# LAN8830_PINOUT.net
KiCad netlist of a schematic drawn in Altium Designer
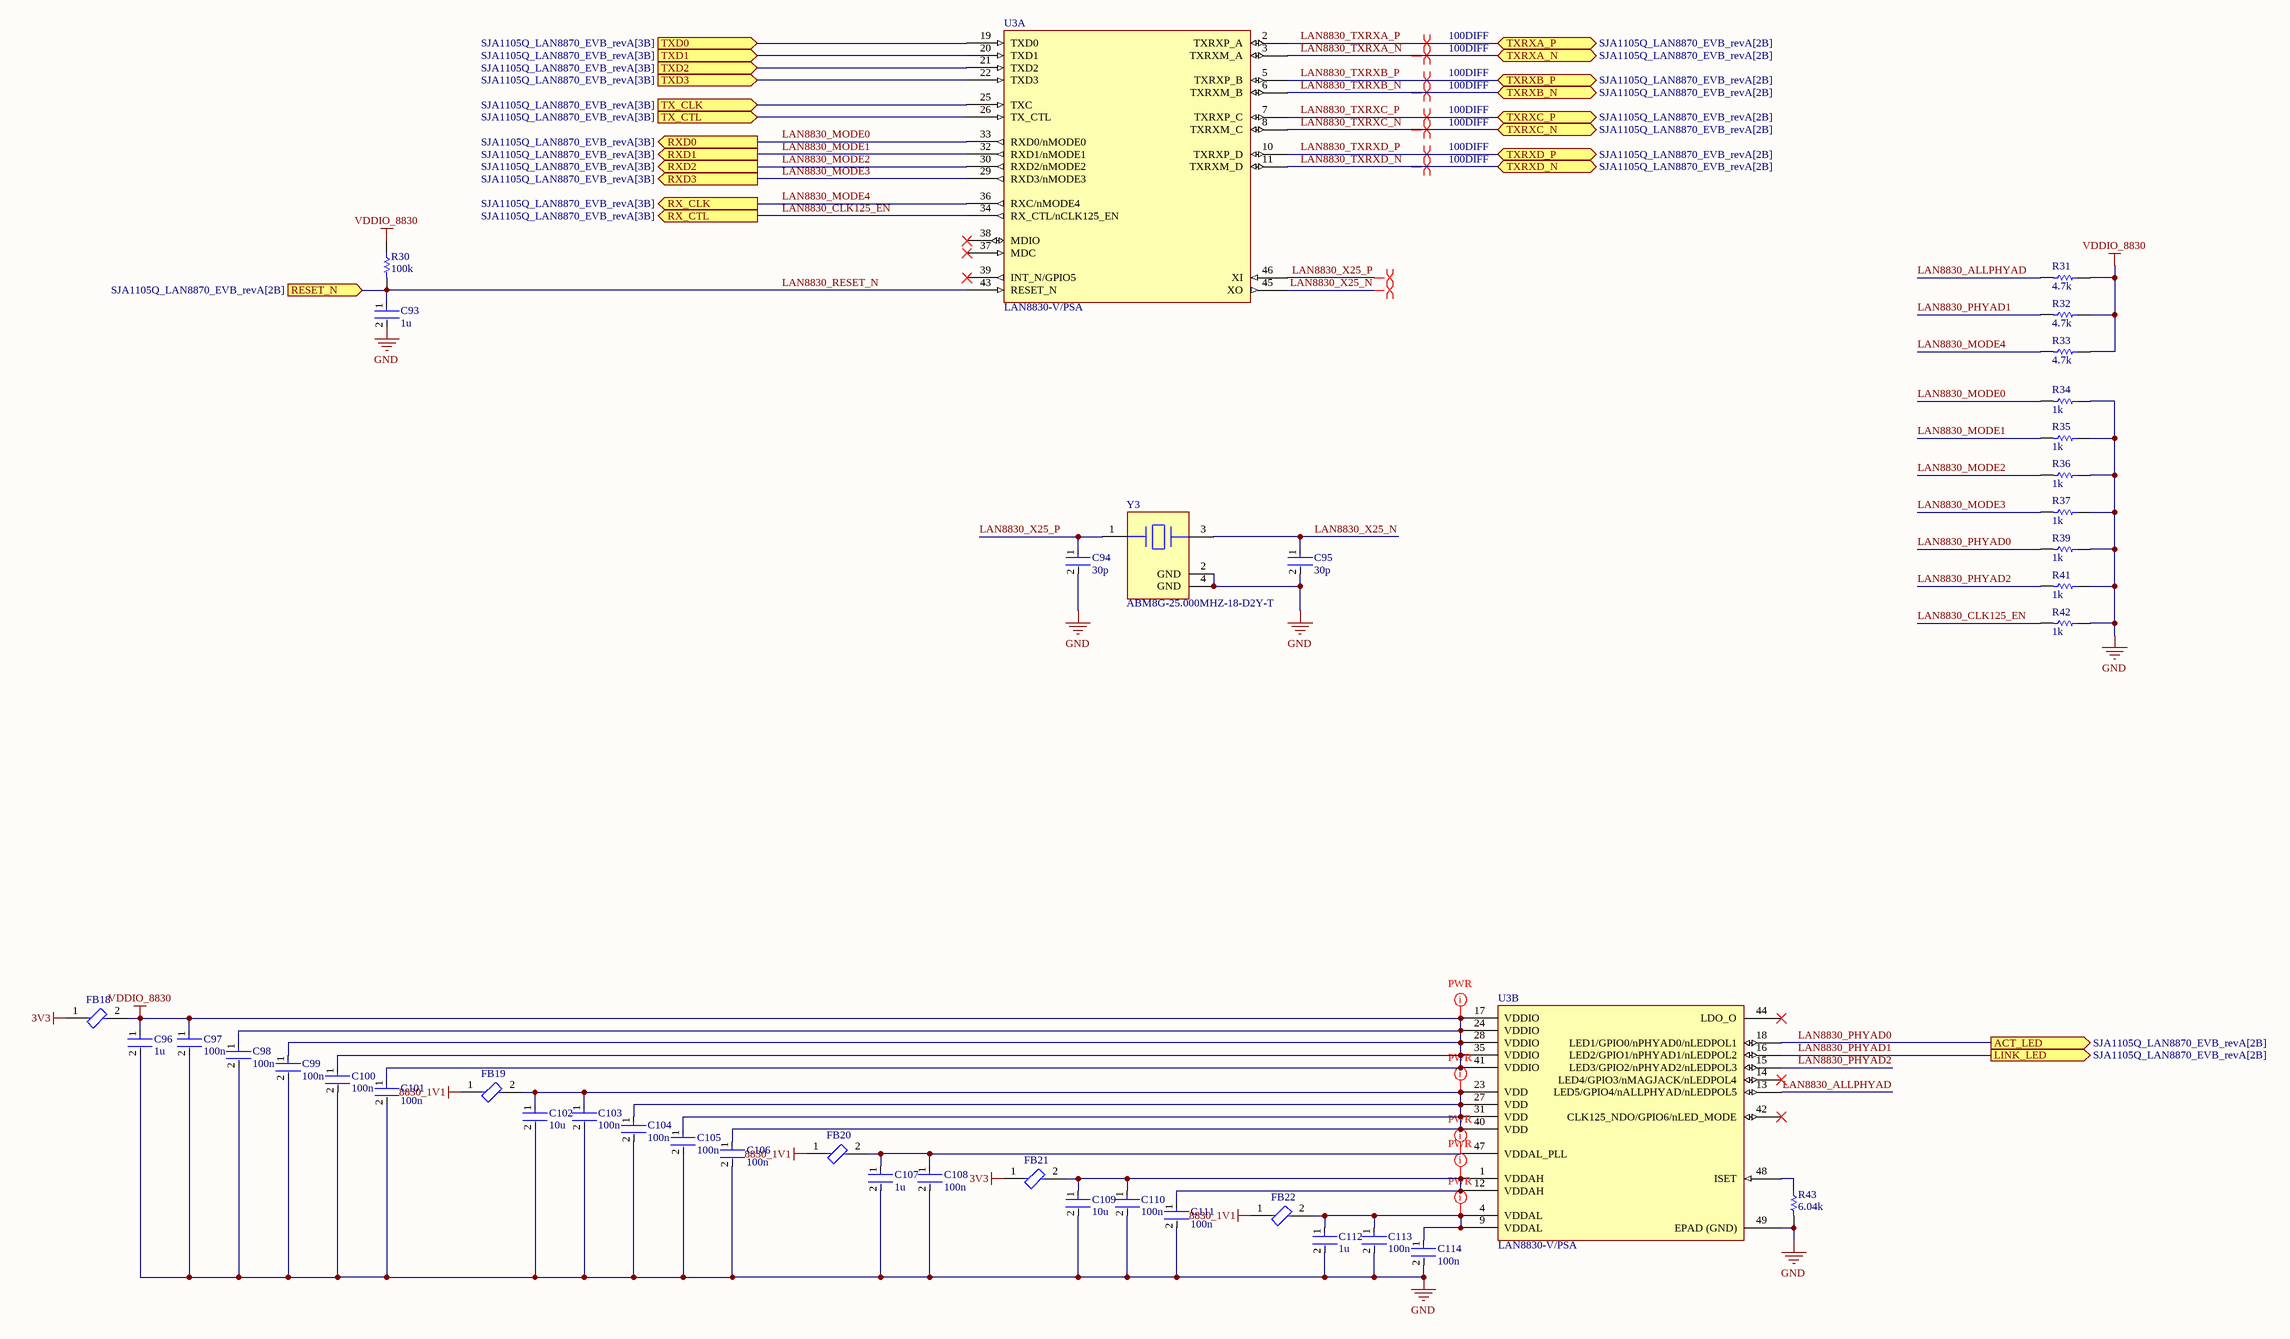
[diagram p0: LAN8830_PINOUT.SchDoc]

(export (version "E")
  (design (tool "Eeschema 10.0.6"))
  (components
    (comp (ref "C93")
      (value "1u")
      (footprint "FP-0402-L_1_0_0_05-W_0_5-IPC_A")
      (description "LARGE PADS, 0402 CAP, CHANGE COMMENT TO MATCH REAL P/N")
      (libsource (lib "Space Concordia") (part "b4654b650e69147ec39a6b967a45e02"))
    )
    (comp (ref "C94")
      (value "30p")
      (footprint "FP-0402-L_1_0_0_05-W_0_5-IPC_A")
      (description "LARGE PADS, 0402 CAP, CHANGE COMMENT TO MATCH REAL P/N")
      (libsource (lib "Space Concordia") (part "b4654b650e69147ec39a6b967a45e02"))
    )
    (comp (ref "C95")
      (value "30p")
      (footprint "FP-0402-L_1_0_0_05-W_0_5-IPC_A")
      (description "LARGE PADS, 0402 CAP, CHANGE COMMENT TO MATCH REAL P/N")
      (libsource (lib "Space Concordia") (part "b4654b650e69147ec39a6b967a45e02"))
    )
    (comp (ref "C96")
      (value "1u")
      (footprint "FP-0402-L_1_0_0_05-W_0_5-IPC_A")
      (description "LARGE PADS, 0402 CAP, CHANGE COMMENT TO MATCH REAL P/N")
      (libsource (lib "Space Concordia") (part "b4654b650e69147ec39a6b967a45e02"))
    )
    (comp (ref "C97")
      (value "100n")
      (footprint "FP-0402-L_1_0_0_05-W_0_5-IPC_A")
      (description "LARGE PADS, 0402 CAP, CHANGE COMMENT TO MATCH REAL P/N")
      (libsource (lib "Space Concordia") (part "b4654b650e69147ec39a6b967a45e02"))
    )
    (comp (ref "C98")
      (value "100n")
      (footprint "FP-0402-L_1_0_0_05-W_0_5-IPC_A")
      (description "LARGE PADS, 0402 CAP, CHANGE COMMENT TO MATCH REAL P/N")
      (libsource (lib "Space Concordia") (part "b4654b650e69147ec39a6b967a45e02"))
    )
    (comp (ref "C99")
      (value "100n")
      (footprint "FP-0402-L_1_0_0_05-W_0_5-IPC_A")
      (description "LARGE PADS, 0402 CAP, CHANGE COMMENT TO MATCH REAL P/N")
      (libsource (lib "Space Concordia") (part "b4654b650e69147ec39a6b967a45e02"))
    )
    (comp (ref "C100")
      (value "100n")
      (footprint "FP-0402-L_1_0_0_05-W_0_5-IPC_A")
      (description "LARGE PADS, 0402 CAP, CHANGE COMMENT TO MATCH REAL P/N")
      (libsource (lib "Space Concordia") (part "b4654b650e69147ec39a6b967a45e02"))
    )
    (comp (ref "C101")
      (value "100n")
      (footprint "FP-0402-L_1_0_0_05-W_0_5-IPC_A")
      (description "LARGE PADS, 0402 CAP, CHANGE COMMENT TO MATCH REAL P/N")
      (libsource (lib "Space Concordia") (part "b4654b650e69147ec39a6b967a45e02"))
    )
    (comp (ref "C102")
      (value "10u")
      (footprint "FP-0402-L_1_0_0_05-W_0_5-IPC_A")
      (description "LARGE PADS, 0402 CAP, CHANGE COMMENT TO MATCH REAL P/N")
      (libsource (lib "Space Concordia") (part "b4654b650e69147ec39a6b967a45e02"))
    )
    (comp (ref "C103")
      (value "100n")
      (footprint "FP-0402-L_1_0_0_05-W_0_5-IPC_A")
      (description "LARGE PADS, 0402 CAP, CHANGE COMMENT TO MATCH REAL P/N")
      (libsource (lib "Space Concordia") (part "b4654b650e69147ec39a6b967a45e02"))
    )
    (comp (ref "C104")
      (value "100n")
      (footprint "FP-0402-L_1_0_0_05-W_0_5-IPC_A")
      (description "LARGE PADS, 0402 CAP, CHANGE COMMENT TO MATCH REAL P/N")
      (libsource (lib "Space Concordia") (part "b4654b650e69147ec39a6b967a45e02"))
    )
    (comp (ref "C105")
      (value "100n")
      (footprint "FP-0402-L_1_0_0_05-W_0_5-IPC_A")
      (description "LARGE PADS, 0402 CAP, CHANGE COMMENT TO MATCH REAL P/N")
      (libsource (lib "Space Concordia") (part "b4654b650e69147ec39a6b967a45e02"))
    )
    (comp (ref "C106")
      (value "100n")
      (footprint "FP-0402-L_1_0_0_05-W_0_5-IPC_A")
      (description "LARGE PADS, 0402 CAP, CHANGE COMMENT TO MATCH REAL P/N")
      (libsource (lib "Space Concordia") (part "b4654b650e69147ec39a6b967a45e02"))
    )
    (comp (ref "C107")
      (value "1u")
      (footprint "FP-0402-L_1_0_0_05-W_0_5-IPC_A")
      (description "LARGE PADS, 0402 CAP, CHANGE COMMENT TO MATCH REAL P/N")
      (libsource (lib "Space Concordia") (part "b4654b650e69147ec39a6b967a45e02"))
    )
    (comp (ref "C108")
      (value "100n")
      (footprint "FP-0402-L_1_0_0_05-W_0_5-IPC_A")
      (description "LARGE PADS, 0402 CAP, CHANGE COMMENT TO MATCH REAL P/N")
      (libsource (lib "Space Concordia") (part "b4654b650e69147ec39a6b967a45e02"))
    )
    (comp (ref "C109")
      (value "10u")
      (footprint "FP-0402-L_1_0_0_05-W_0_5-IPC_A")
      (description "LARGE PADS, 0402 CAP, CHANGE COMMENT TO MATCH REAL P/N")
      (libsource (lib "Space Concordia") (part "b4654b650e69147ec39a6b967a45e02"))
    )
    (comp (ref "C110")
      (value "100n")
      (footprint "FP-0402-L_1_0_0_05-W_0_5-IPC_A")
      (description "LARGE PADS, 0402 CAP, CHANGE COMMENT TO MATCH REAL P/N")
      (libsource (lib "Space Concordia") (part "b4654b650e69147ec39a6b967a45e02"))
    )
    (comp (ref "C111")
      (value "100n")
      (footprint "FP-0402-L_1_0_0_05-W_0_5-IPC_A")
      (description "LARGE PADS, 0402 CAP, CHANGE COMMENT TO MATCH REAL P/N")
      (libsource (lib "Space Concordia") (part "b4654b650e69147ec39a6b967a45e02"))
    )
    (comp (ref "C112")
      (value "1u")
      (footprint "FP-0402-L_1_0_0_05-W_0_5-IPC_A")
      (description "LARGE PADS, 0402 CAP, CHANGE COMMENT TO MATCH REAL P/N")
      (libsource (lib "Space Concordia") (part "b4654b650e69147ec39a6b967a45e02"))
    )
    (comp (ref "C113")
      (value "100n")
      (footprint "FP-0402-L_1_0_0_05-W_0_5-IPC_A")
      (description "LARGE PADS, 0402 CAP, CHANGE COMMENT TO MATCH REAL P/N")
      (libsource (lib "Space Concordia") (part "b4654b650e69147ec39a6b967a45e02"))
    )
    (comp (ref "C114")
      (value "100n")
      (footprint "FP-0402-L_1_0_0_05-W_0_5-IPC_A")
      (description "LARGE PADS, 0402 CAP, CHANGE COMMENT TO MATCH REAL P/N")
      (libsource (lib "Space Concordia") (part "b4654b650e69147ec39a6b967a45e02"))
    )
    (comp (ref "FB18")
      (value "BLM18KG331SH1D")
      (footprint "FP-BLM18-0_15-t0_8-IPC_B")
      (description "Chip Ferrite Bead, 0603, 330Ω @ 100MHz, 0.08Ω, 25%, 1.7A")
      (libsource (lib "Altium Content Vault") (part "5f30dd21d616792df468990f7003faa"))
    )
    (comp (ref "FB19")
      (value "BLM18KG331SH1D")
      (footprint "FP-BLM18-0_15-t0_8-IPC_B")
      (description "Chip Ferrite Bead, 0603, 330Ω @ 100MHz, 0.08Ω, 25%, 1.7A")
      (libsource (lib "Altium Content Vault") (part "5f30dd21d616792df468990f7003faa"))
    )
    (comp (ref "FB20")
      (value "BLM18KG331SH1D")
      (footprint "FP-BLM18-0_15-t0_8-IPC_B")
      (description "Chip Ferrite Bead, 0603, 330Ω @ 100MHz, 0.08Ω, 25%, 1.7A")
      (libsource (lib "Altium Content Vault") (part "5f30dd21d616792df468990f7003faa"))
    )
    (comp (ref "FB21")
      (value "BLM18KG331SH1D")
      (footprint "FP-BLM18-0_15-t0_8-IPC_B")
      (description "Chip Ferrite Bead, 0603, 330Ω @ 100MHz, 0.08Ω, 25%, 1.7A")
      (libsource (lib "Altium Content Vault") (part "5f30dd21d616792df468990f7003faa"))
    )
    (comp (ref "FB22")
      (value "BLM18KG331SH1D")
      (footprint "FP-BLM18-0_15-t0_8-IPC_B")
      (description "Chip Ferrite Bead, 0603, 330Ω @ 100MHz, 0.08Ω, 25%, 1.7A")
      (libsource (lib "Altium Content Vault") (part "5f30dd21d616792df468990f7003faa"))
    )
    (comp (ref "R30")
      (value "100k")
      (footprint "R0603B")
      (description "Resistor")
      (libsource (lib "Space Concordia") (part "Resistor"))
    )
    (comp (ref "R31")
      (value "4.7k")
      (footprint "R0603B")
      (description "Resistor")
      (libsource (lib "Space Concordia") (part "Resistor"))
    )
    (comp (ref "R32")
      (value "4.7k")
      (footprint "R0603B")
      (description "Resistor")
      (libsource (lib "Space Concordia") (part "Resistor"))
    )
    (comp (ref "R33")
      (value "4.7k")
      (footprint "R0603B")
      (description "Resistor")
      (libsource (lib "Space Concordia") (part "Resistor"))
    )
    (comp (ref "R34")
      (value "1k")
      (footprint "R0603B")
      (description "Resistor")
      (libsource (lib "Space Concordia") (part "Resistor"))
    )
    (comp (ref "R35")
      (value "1k")
      (footprint "R0603B")
      (description "Resistor")
      (libsource (lib "Space Concordia") (part "Resistor"))
    )
    (comp (ref "R36")
      (value "1k")
      (footprint "R0603B")
      (description "Resistor")
      (libsource (lib "Space Concordia") (part "Resistor"))
    )
    (comp (ref "R37")
      (value "1k")
      (footprint "R0603B")
      (description "Resistor")
      (libsource (lib "Space Concordia") (part "Resistor"))
    )
    (comp (ref "R39")
      (value "1k")
      (footprint "R0603B")
      (description "Resistor")
      (libsource (lib "Space Concordia") (part "Resistor"))
    )
    (comp (ref "R41")
      (value "1k")
      (footprint "R0603B")
      (description "Resistor")
      (libsource (lib "Space Concordia") (part "Resistor"))
    )
    (comp (ref "R42")
      (value "1k")
      (footprint "R0603B")
      (description "Resistor")
      (libsource (lib "Space Concordia") (part "Resistor"))
    )
    (comp (ref "R43")
      (value "6.04k")
      (footprint "R0603B")
      (description "Resistor")
      (libsource (lib "Space Concordia") (part "Resistor"))
    )
    (comp (ref "U3")
      (value "LAN8830-V/PSA")
      (footprint "QFN50P700X700X100_HS-49N")
      (description "LAN8830 Series RGMII Interface Gigabit Ethernet Transceiver - VQFN-48")
      (libsource (lib "Space Concordia") (part "LAN8830-V_PSA"))
    )
    (comp (ref "Y3")
      (value "ABM8G-25.000MHZ-18-D2Y-T")
      (footprint "FP-ABM8G-MFG")
      (description "Crystal 25MHz ±20ppm (Tol) ±30ppm (Stability) 18pF FUND 60Ω 4-Pin SMD T/R")
      (fields (field (name "TOLERANCE") "20ppm"))
      (libsource (lib "Altium Content Vault") (part "48e526d86b7f2615d98721063c72f49"))
    )
  )
  (nets
    (net (code "1") (name "/LAN8830_ALLPHYAD") (class "Default")
      (node (ref "R31") (pin "2") (pinfunction "2_2") (pintype "passive"))
      (node (ref "U3") (pin "13") (pinfunction "LED5/GPIO4/nALLPHYAD/nLEDPOL5_13") (pintype "bidirectional"))
    )
    (net (code "2") (name "/LAN8830_CLK125_EN") (class "Default")
      (node (ref "R42") (pin "2") (pinfunction "2_2") (pintype "passive"))
      (node (ref "U3") (pin "34") (pinfunction "RX_CTL/nCLK125_EN_34") (pintype "output"))
    )
    (net (code "3") (name "/LAN8830_MODE0") (class "Default")
      (node (ref "R34") (pin "2") (pinfunction "2_2") (pintype "passive"))
      (node (ref "U3") (pin "33") (pinfunction "RXD0/nMODE0_33") (pintype "output"))
    )
    (net (code "4") (name "/LAN8830_MODE1") (class "Default")
      (node (ref "R35") (pin "2") (pinfunction "2_2") (pintype "passive"))
      (node (ref "U3") (pin "32") (pinfunction "RXD1/nMODE1_32") (pintype "output"))
    )
    (net (code "5") (name "/LAN8830_MODE2") (class "Default")
      (node (ref "R36") (pin "2") (pinfunction "2_2") (pintype "passive"))
      (node (ref "U3") (pin "30") (pinfunction "RXD2/nMODE2_30") (pintype "output"))
    )
    (net (code "6") (name "/LAN8830_MODE3") (class "Default")
      (node (ref "R37") (pin "2") (pinfunction "2_2") (pintype "passive"))
      (node (ref "U3") (pin "29") (pinfunction "RXD3/nMODE3_29") (pintype "output"))
    )
    (net (code "7") (name "/LAN8830_MODE4") (class "Default")
      (node (ref "R33") (pin "2") (pinfunction "2_2") (pintype "passive"))
      (node (ref "U3") (pin "36") (pinfunction "RXC/nMODE4_36") (pintype "output"))
    )
    (net (code "8") (name "/LAN8830_PHYAD0") (class "Default")
      (node (ref "R39") (pin "2") (pinfunction "2_2") (pintype "passive"))
      (node (ref "U3") (pin "18") (pinfunction "LED1/GPIO0/nPHYAD0/nLEDPOL1_18") (pintype "bidirectional"))
    )
    (net (code "9") (name "/LAN8830_PHYAD1") (class "Default")
      (node (ref "R32") (pin "2") (pinfunction "2_2") (pintype "passive"))
      (node (ref "U3") (pin "16") (pinfunction "LED2/GPIO1/nPHYAD1/nLEDPOL2_16") (pintype "bidirectional"))
    )
    (net (code "10") (name "/LAN8830_PHYAD2") (class "Default")
      (node (ref "R41") (pin "2") (pinfunction "2_2") (pintype "passive"))
      (node (ref "U3") (pin "15") (pinfunction "LED3/GPIO2/nPHYAD2/nLEDPOL3_15") (pintype "bidirectional"))
    )
    (net (code "11") (name "/LAN8830_RESET_N") (class "Default")
      (node (ref "C93") (pin "1") (pinfunction "1_1") (pintype "passive"))
      (node (ref "R30") (pin "2") (pinfunction "2_2") (pintype "passive"))
      (node (ref "U3") (pin "43") (pinfunction "RESET_N_43") (pintype "input"))
    )
    (net (code "12") (name "/LAN8830_TXRXA_N") (class "Default")
      (node (ref "U3") (pin "3") (pinfunction "TXRXM_A_3") (pintype "bidirectional"))
    )
    (net (code "13") (name "/LAN8830_TXRXA_P") (class "Default")
      (node (ref "U3") (pin "2") (pinfunction "TXRXP_A_2") (pintype "bidirectional"))
    )
    (net (code "14") (name "/LAN8830_TXRXB_N") (class "Default")
      (node (ref "U3") (pin "6") (pinfunction "TXRXM_B_6") (pintype "bidirectional"))
    )
    (net (code "15") (name "/LAN8830_TXRXB_P") (class "Default")
      (node (ref "U3") (pin "5") (pinfunction "TXRXP_B_5") (pintype "bidirectional"))
    )
    (net (code "16") (name "/LAN8830_TXRXC_N") (class "Default")
      (node (ref "U3") (pin "8") (pinfunction "TXRXM_C_8") (pintype "bidirectional"))
    )
    (net (code "17") (name "/LAN8830_TXRXC_P") (class "Default")
      (node (ref "U3") (pin "7") (pinfunction "TXRXP_C_7") (pintype "bidirectional"))
    )
    (net (code "18") (name "/LAN8830_TXRXD_N") (class "Default")
      (node (ref "U3") (pin "11") (pinfunction "TXRXM_D_11") (pintype "bidirectional"))
    )
    (net (code "19") (name "/LAN8830_TXRXD_P") (class "Default")
      (node (ref "U3") (pin "10") (pinfunction "TXRXP_D_10") (pintype "bidirectional"))
    )
    (net (code "20") (name "/LAN8830_X25_N") (class "Default")
      (node (ref "C95") (pin "1") (pinfunction "1_1") (pintype "passive"))
      (node (ref "U3") (pin "45") (pinfunction "XO_45") (pintype "output"))
      (node (ref "Y3") (pin "3") (pinfunction "3_3") (pintype "passive"))
    )
    (net (code "21") (name "/LAN8830_X25_P") (class "Default")
      (node (ref "C94") (pin "1") (pinfunction "1_1") (pintype "passive"))
      (node (ref "U3") (pin "46") (pinfunction "XI_46") (pintype "input"))
      (node (ref "Y3") (pin "1") (pinfunction "1_1") (pintype "passive"))
    )
    (net (code "22") (name "/TXD0") (class "Default")
      (node (ref "U3") (pin "19") (pinfunction "TXD0_19") (pintype "input"))
    )
    (net (code "23") (name "/TXD1") (class "Default")
      (node (ref "U3") (pin "20") (pinfunction "TXD1_20") (pintype "input"))
    )
    (net (code "24") (name "/TXD2") (class "Default")
      (node (ref "U3") (pin "21") (pinfunction "TXD2_21") (pintype "input"))
    )
    (net (code "25") (name "/TXD3") (class "Default")
      (node (ref "U3") (pin "22") (pinfunction "TXD3_22") (pintype "input"))
    )
    (net (code "26") (name "/TX_CLK") (class "Default")
      (node (ref "U3") (pin "25") (pinfunction "TXC_25") (pintype "input"))
    )
    (net (code "27") (name "/TX_CTL") (class "Default")
      (node (ref "U3") (pin "26") (pinfunction "TX_CTL_26") (pintype "input"))
    )
    (net (code "28") (name "3V3") (class "Default")
      (node (ref "FB18") (pin "1") (pinfunction "1_1") (pintype "passive"))
      (node (ref "FB21") (pin "1") (pinfunction "1_1") (pintype "passive"))
    )
    (net (code "29") (name "8830_1V1") (class "Default")
      (node (ref "FB19") (pin "1") (pinfunction "1_1") (pintype "passive"))
      (node (ref "FB20") (pin "1") (pinfunction "1_1") (pintype "passive"))
      (node (ref "FB22") (pin "1") (pinfunction "1_1") (pintype "passive"))
    )
    (net (code "30") (name "GND") (class "Default")
      (node (ref "C100") (pin "2") (pinfunction "2_2") (pintype "passive"))
      (node (ref "C101") (pin "2") (pinfunction "2_2") (pintype "passive"))
      (node (ref "C102") (pin "2") (pinfunction "2_2") (pintype "passive"))
      (node (ref "C103") (pin "2") (pinfunction "2_2") (pintype "passive"))
      (node (ref "C104") (pin "2") (pinfunction "2_2") (pintype "passive"))
      (node (ref "C105") (pin "2") (pinfunction "2_2") (pintype "passive"))
      (node (ref "C106") (pin "2") (pinfunction "2_2") (pintype "passive"))
      (node (ref "C107") (pin "2") (pinfunction "2_2") (pintype "passive"))
      (node (ref "C108") (pin "2") (pinfunction "2_2") (pintype "passive"))
      (node (ref "C109") (pin "2") (pinfunction "2_2") (pintype "passive"))
      (node (ref "C110") (pin "2") (pinfunction "2_2") (pintype "passive"))
      (node (ref "C111") (pin "2") (pinfunction "2_2") (pintype "passive"))
      (node (ref "C112") (pin "2") (pinfunction "2_2") (pintype "passive"))
      (node (ref "C113") (pin "2") (pinfunction "2_2") (pintype "passive"))
      (node (ref "C114") (pin "2") (pinfunction "2_2") (pintype "passive"))
      (node (ref "C93") (pin "2") (pinfunction "2_2") (pintype "passive"))
      (node (ref "C94") (pin "2") (pinfunction "2_2") (pintype "passive"))
      (node (ref "C95") (pin "2") (pinfunction "2_2") (pintype "passive"))
      (node (ref "C96") (pin "2") (pinfunction "2_2") (pintype "passive"))
      (node (ref "C97") (pin "2") (pinfunction "2_2") (pintype "passive"))
      (node (ref "C98") (pin "2") (pinfunction "2_2") (pintype "passive"))
      (node (ref "C99") (pin "2") (pinfunction "2_2") (pintype "passive"))
      (node (ref "R34") (pin "1") (pinfunction "1_1") (pintype "passive"))
      (node (ref "R35") (pin "1") (pinfunction "1_1") (pintype "passive"))
      (node (ref "R36") (pin "1") (pinfunction "1_1") (pintype "passive"))
      (node (ref "R37") (pin "1") (pinfunction "1_1") (pintype "passive"))
      (node (ref "R39") (pin "1") (pinfunction "1_1") (pintype "passive"))
      (node (ref "R41") (pin "1") (pinfunction "1_1") (pintype "passive"))
      (node (ref "R42") (pin "1") (pinfunction "1_1") (pintype "passive"))
      (node (ref "R43") (pin "2") (pinfunction "2_2") (pintype "passive"))
      (node (ref "U3") (pin "49") (pinfunction "EPAD_(GND)_49") (pintype "power_in"))
      (node (ref "Y3") (pin "2") (pinfunction "GND_2") (pintype "power_in"))
      (node (ref "Y3") (pin "4") (pinfunction "GND_4") (pintype "power_in"))
    )
    (net (code "31") (name "Net-(C102-Pad1)") (class "Default")
      (node (ref "C102") (pin "1") (pinfunction "1_1") (pintype "passive"))
      (node (ref "C103") (pin "1") (pinfunction "1_1") (pintype "passive"))
      (node (ref "C104") (pin "1") (pinfunction "1_1") (pintype "passive"))
      (node (ref "C105") (pin "1") (pinfunction "1_1") (pintype "passive"))
      (node (ref "C106") (pin "1") (pinfunction "1_1") (pintype "passive"))
      (node (ref "FB19") (pin "2") (pinfunction "2_2") (pintype "passive"))
      (node (ref "U3") (pin "23") (pinfunction "VDD_23") (pintype "power_in"))
      (node (ref "U3") (pin "27") (pinfunction "VDD_27") (pintype "power_in"))
      (node (ref "U3") (pin "31") (pinfunction "VDD_31") (pintype "power_in"))
      (node (ref "U3") (pin "40") (pinfunction "VDD_40") (pintype "power_in"))
    )
    (net (code "32") (name "Net-(C109-Pad1)") (class "Default")
      (node (ref "C109") (pin "1") (pinfunction "1_1") (pintype "passive"))
      (node (ref "C110") (pin "1") (pinfunction "1_1") (pintype "passive"))
      (node (ref "C111") (pin "1") (pinfunction "1_1") (pintype "passive"))
      (node (ref "FB21") (pin "2") (pinfunction "2_2") (pintype "passive"))
      (node (ref "U3") (pin "1") (pinfunction "VDDAH_1") (pintype "power_in"))
      (node (ref "U3") (pin "12") (pinfunction "VDDAH_12") (pintype "power_in"))
    )
    (net (code "33") (name "Net-(C112-Pad1)") (class "Default")
      (node (ref "C112") (pin "1") (pinfunction "1_1") (pintype "passive"))
      (node (ref "C113") (pin "1") (pinfunction "1_1") (pintype "passive"))
      (node (ref "C114") (pin "1") (pinfunction "1_1") (pintype "passive"))
      (node (ref "FB22") (pin "2") (pinfunction "2_2") (pintype "passive"))
      (node (ref "U3") (pin "4") (pinfunction "VDDAL_4") (pintype "power_in"))
      (node (ref "U3") (pin "9") (pinfunction "VDDAL_9") (pintype "power_in"))
    )
    (net (code "34") (name "Net-(U3B-ISET)") (class "Default")
      (node (ref "R43") (pin "1") (pinfunction "1_1") (pintype "passive"))
      (node (ref "U3") (pin "48") (pinfunction "ISET_48") (pintype "input"))
    )
    (net (code "35") (name "Net-(U3B-VDDAL_PLL)") (class "Default")
      (node (ref "C107") (pin "1") (pinfunction "1_1") (pintype "passive"))
      (node (ref "C108") (pin "1") (pinfunction "1_1") (pintype "passive"))
      (node (ref "FB20") (pin "2") (pinfunction "2_2") (pintype "passive"))
      (node (ref "U3") (pin "47") (pinfunction "VDDAL_PLL_47") (pintype "power_in"))
    )
    (net (code "36") (name "VDDIO_8830") (class "Default")
      (node (ref "C100") (pin "1") (pinfunction "1_1") (pintype "passive"))
      (node (ref "C101") (pin "1") (pinfunction "1_1") (pintype "passive"))
      (node (ref "C96") (pin "1") (pinfunction "1_1") (pintype "passive"))
      (node (ref "C97") (pin "1") (pinfunction "1_1") (pintype "passive"))
      (node (ref "C98") (pin "1") (pinfunction "1_1") (pintype "passive"))
      (node (ref "C99") (pin "1") (pinfunction "1_1") (pintype "passive"))
      (node (ref "FB18") (pin "2") (pinfunction "2_2") (pintype "passive"))
      (node (ref "R30") (pin "1") (pinfunction "1_1") (pintype "passive"))
      (node (ref "R31") (pin "1") (pinfunction "1_1") (pintype "passive"))
      (node (ref "R32") (pin "1") (pinfunction "1_1") (pintype "passive"))
      (node (ref "R33") (pin "1") (pinfunction "1_1") (pintype "passive"))
      (node (ref "U3") (pin "17") (pinfunction "VDDIO_17") (pintype "power_in"))
      (node (ref "U3") (pin "24") (pinfunction "VDDIO_24") (pintype "power_in"))
      (node (ref "U3") (pin "28") (pinfunction "VDDIO_28") (pintype "power_in"))
      (node (ref "U3") (pin "35") (pinfunction "VDDIO_35") (pintype "power_in"))
      (node (ref "U3") (pin "41") (pinfunction "VDDIO_41") (pintype "power_in"))
    )
    (net (code "37") (name "unconnected-(U3A-INT_N{slash}GPIO5-Pad39)") (class "Default")
      (node (ref "U3") (pin "39") (pinfunction "INT_N/GPIO5_39") (pintype "output+no_connect"))
    )
    (net (code "38") (name "unconnected-(U3A-MDC-Pad37)") (class "Default")
      (node (ref "U3") (pin "37") (pinfunction "MDC_37") (pintype "input+no_connect"))
    )
    (net (code "39") (name "unconnected-(U3A-MDIO-Pad38)") (class "Default")
      (node (ref "U3") (pin "38") (pinfunction "MDIO_38") (pintype "bidirectional+no_connect"))
    )
    (net (code "40") (name "unconnected-(U3B-CLK125_NDO{slash}GPIO6{slash}nLED_MODE-Pad42)") (class "Default")
      (node (ref "U3") (pin "42") (pinfunction "CLK125_NDO/GPIO6/nLED_MODE_42") (pintype "bidirectional+no_connect"))
    )
    (net (code "41") (name "unconnected-(U3B-LDO_O-Pad44)") (class "Default")
      (node (ref "U3") (pin "44") (pinfunction "LDO_O_44") (pintype "power_in+no_connect"))
    )
    (net (code "42") (name "unconnected-(U3B-LED4{slash}GPIO3{slash}nMAGJACK{slash}nLEDPOL4-Pad14)") (class "Default")
      (node (ref "U3") (pin "14") (pinfunction "LED4/GPIO3/nMAGJACK/nLEDPOL4_14") (pintype "bidirectional+no_connect"))
    )
  )
)
